# schematic.net
KiCad netlist of a schematic drawn in EAGLE
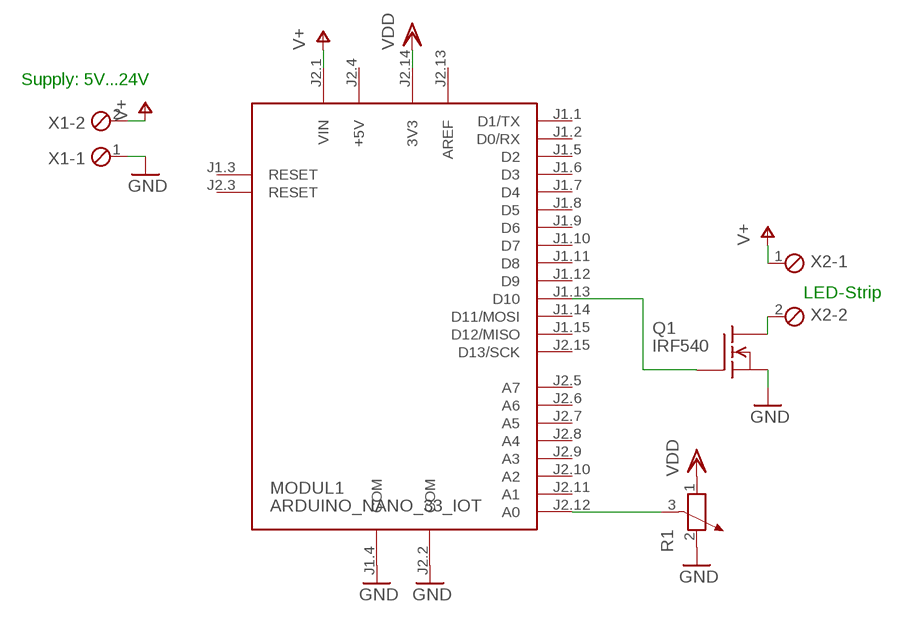
[diagram p0: schematic, sheet 1]

(export (version "E")
  (design (tool "Eeschema 10.0.6"))
  (components
    (comp (ref "MODUL1")
      (value "ARDUINO_NANO_33_IOT")
      (footprint "eagle-import:ARDUINO_NANO2")
      (libsource (lib "eagle-import") (part "ARDUINO_NANO_33_IOT"))
    )
    (comp (ref "Q1")
      (value "IRF540")
      (footprint "eagle-import:TO220")
      (libsource (lib "eagle-import") (part "IRF540"))
    )
    (comp (ref "R1")
      (value "POTENTIOMETER_PT-10")
      (footprint "eagle-import:PT-10")
      (libsource (lib "eagle-import") (part "POTENTIOMETER_PT-10"))
    )
    (comp (ref "X1")
      (value "MPT2")
      (footprint "eagle-import:2POL254")
      (libsource (lib "eagle-import") (part "MPT2"))
    )
    (comp (ref "X2")
      (value "MPT2")
      (footprint "eagle-import:2POL254")
      (libsource (lib "eagle-import") (part "MPT2"))
    )
  )
  (nets
    (net (code "1") (name "/+5V") (class "Default")
      (node (ref "MODUL1") (pin "J2.4") (pinfunction "+5V_J2.4") (pintype "power_in"))
    )
    (net (code "2") (name "/AREF") (class "Default")
      (node (ref "MODUL1") (pin "J2.13") (pinfunction "AREF_J2.13") (pintype "power_in"))
    )
    (net (code "3") (name "GND") (class "Default")
      (node (ref "MODUL1") (pin "J1.4") (pinfunction "COM_J1.4") (pintype "power_in"))
      (node (ref "MODUL1") (pin "J2.2") (pinfunction "COM_J2.2") (pintype "power_in"))
      (node (ref "Q1") (pin "3") (pinfunction "S_3") (pintype "passive"))
      (node (ref "R1") (pin "2") (pinfunction "2_2") (pintype "passive"))
      (node (ref "X1") (pin "1") (pinfunction "1_1") (pintype "passive"))
    )
    (net (code "4") (name "Net-(MODUL1-A0)") (class "Default")
      (node (ref "MODUL1") (pin "J2.12") (pinfunction "A0_J2.12") (pintype "bidirectional"))
      (node (ref "R1") (pin "3") (pinfunction "3_3") (pintype "passive"))
    )
    (net (code "5") (name "Net-(MODUL1-D10)") (class "Default")
      (node (ref "MODUL1") (pin "J1.13") (pinfunction "D10_J1.13") (pintype "bidirectional"))
      (node (ref "Q1") (pin "1") (pinfunction "G_1") (pintype "passive"))
    )
    (net (code "6") (name "Net-(Q1-D)") (class "Default")
      (node (ref "Q1") (pin "2") (pinfunction "D_2") (pintype "passive"))
      (node (ref "X2") (pin "2") (pinfunction "1_2") (pintype "passive"))
    )
    (net (code "7") (name "V+") (class "Default")
      (node (ref "MODUL1") (pin "J2.1") (pinfunction "VIN_J2.1") (pintype "power_in"))
      (node (ref "X1") (pin "2") (pinfunction "1_2") (pintype "passive"))
      (node (ref "X2") (pin "1") (pinfunction "1_1") (pintype "passive"))
    )
    (net (code "8") (name "VDD") (class "Default")
      (node (ref "MODUL1") (pin "J2.14") (pinfunction "3V3_J2.14") (pintype "power_in"))
      (node (ref "R1") (pin "1") (pinfunction "1_1") (pintype "passive"))
    )
    (net (code "9") (name "unconnected-(MODUL1-A1-PadJ2.11)") (class "Default")
      (node (ref "MODUL1") (pin "J2.11") (pinfunction "A1_J2.11") (pintype "bidirectional"))
    )
    (net (code "10") (name "unconnected-(MODUL1-A2-PadJ2.10)") (class "Default")
      (node (ref "MODUL1") (pin "J2.10") (pinfunction "A2_J2.10") (pintype "bidirectional"))
    )
    (net (code "11") (name "unconnected-(MODUL1-A3-PadJ2.9)") (class "Default")
      (node (ref "MODUL1") (pin "J2.9") (pinfunction "A3_J2.9") (pintype "bidirectional"))
    )
    (net (code "12") (name "unconnected-(MODUL1-A4-PadJ2.8)") (class "Default")
      (node (ref "MODUL1") (pin "J2.8") (pinfunction "A4_J2.8") (pintype "bidirectional"))
    )
    (net (code "13") (name "unconnected-(MODUL1-A5-PadJ2.7)") (class "Default")
      (node (ref "MODUL1") (pin "J2.7") (pinfunction "A5_J2.7") (pintype "bidirectional"))
    )
    (net (code "14") (name "unconnected-(MODUL1-A6-PadJ2.6)") (class "Default")
      (node (ref "MODUL1") (pin "J2.6") (pinfunction "A6_J2.6") (pintype "bidirectional"))
    )
    (net (code "15") (name "unconnected-(MODUL1-A7-PadJ2.5)") (class "Default")
      (node (ref "MODUL1") (pin "J2.5") (pinfunction "A7_J2.5") (pintype "bidirectional"))
    )
    (net (code "16") (name "unconnected-(MODUL1-D0{slash}RX-PadJ1.2)") (class "Default")
      (node (ref "MODUL1") (pin "J1.2") (pinfunction "D0/RX_J1.2") (pintype "bidirectional"))
    )
    (net (code "17") (name "unconnected-(MODUL1-D1{slash}TX-PadJ1.1)") (class "Default")
      (node (ref "MODUL1") (pin "J1.1") (pinfunction "D1/TX_J1.1") (pintype "bidirectional"))
    )
    (net (code "18") (name "unconnected-(MODUL1-D2-PadJ1.5)") (class "Default")
      (node (ref "MODUL1") (pin "J1.5") (pinfunction "D2_J1.5") (pintype "bidirectional"))
    )
    (net (code "19") (name "unconnected-(MODUL1-D3-PadJ1.6)") (class "Default")
      (node (ref "MODUL1") (pin "J1.6") (pinfunction "D3_J1.6") (pintype "bidirectional"))
    )
    (net (code "20") (name "unconnected-(MODUL1-D4-PadJ1.7)") (class "Default")
      (node (ref "MODUL1") (pin "J1.7") (pinfunction "D4_J1.7") (pintype "bidirectional"))
    )
    (net (code "21") (name "unconnected-(MODUL1-D5-PadJ1.8)") (class "Default")
      (node (ref "MODUL1") (pin "J1.8") (pinfunction "D5_J1.8") (pintype "bidirectional"))
    )
    (net (code "22") (name "unconnected-(MODUL1-D6-PadJ1.9)") (class "Default")
      (node (ref "MODUL1") (pin "J1.9") (pinfunction "D6_J1.9") (pintype "bidirectional"))
    )
    (net (code "23") (name "unconnected-(MODUL1-D7-PadJ1.10)") (class "Default")
      (node (ref "MODUL1") (pin "J1.10") (pinfunction "D7_J1.10") (pintype "bidirectional"))
    )
    (net (code "24") (name "unconnected-(MODUL1-D8-PadJ1.11)") (class "Default")
      (node (ref "MODUL1") (pin "J1.11") (pinfunction "D8_J1.11") (pintype "bidirectional"))
    )
    (net (code "25") (name "unconnected-(MODUL1-D9-PadJ1.12)") (class "Default")
      (node (ref "MODUL1") (pin "J1.12") (pinfunction "D9_J1.12") (pintype "bidirectional"))
    )
    (net (code "26") (name "unconnected-(MODUL1-D11{slash}MOSI-PadJ1.14)") (class "Default")
      (node (ref "MODUL1") (pin "J1.14") (pinfunction "D11/MOSI_J1.14") (pintype "bidirectional"))
    )
    (net (code "27") (name "unconnected-(MODUL1-D12{slash}MISO-PadJ1.15)") (class "Default")
      (node (ref "MODUL1") (pin "J1.15") (pinfunction "D12/MISO_J1.15") (pintype "bidirectional"))
    )
    (net (code "28") (name "unconnected-(MODUL1-D13{slash}SCK-PadJ2.15)") (class "Default")
      (node (ref "MODUL1") (pin "J2.15") (pinfunction "D13/SCK_J2.15") (pintype "bidirectional"))
    )
    (net (code "29") (name "unconnected-(MODUL1-RESET-PadJ1.3)") (class "Default")
      (node (ref "MODUL1") (pin "J1.3") (pinfunction "RESET_J1.3") (pintype "bidirectional"))
    )
    (net (code "30") (name "unconnected-(MODUL1-RESET-PadJ2.3)") (class "Default")
      (node (ref "MODUL1") (pin "J2.3") (pinfunction "RESET_J2.3") (pintype "bidirectional"))
    )
  )
)
